# PCB_MOTEUR_V0_1b.net
KiCad netlist of a schematic drawn in EAGLE
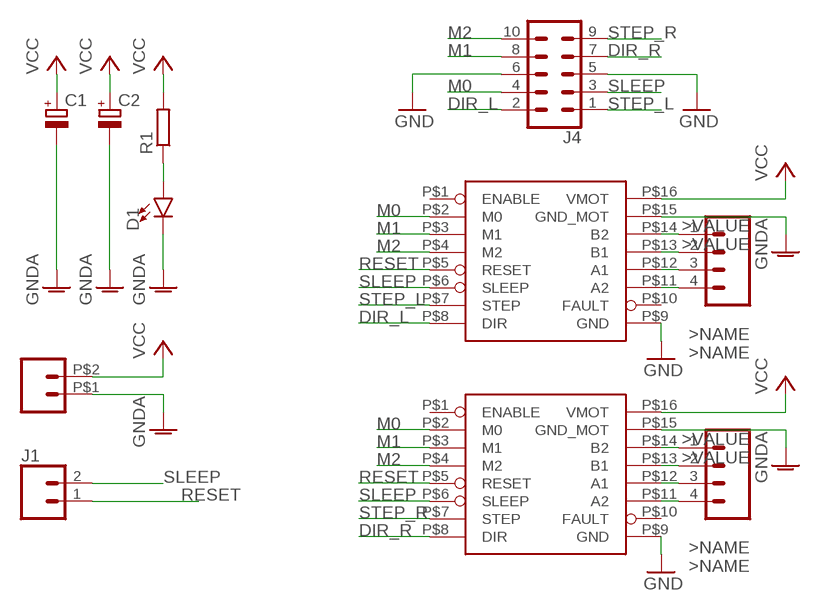
[diagram p0: schematic, sheet 1]

(export (version "E")
  (design (tool "Eeschema 10.0.6"))
  (components
    (comp (ref "C1")
      (value "CPOL-EUE3.5-8")
      (footprint "eagle-import:E3,5-8")
      (libsource (lib "eagle-import") (part "CPOL-EUE3.5-8"))
    )
    (comp (ref "C2")
      (value "CPOL-EUE3.5-8")
      (footprint "eagle-import:E3,5-8")
      (libsource (lib "eagle-import") (part "CPOL-EUE3.5-8"))
    )
    (comp (ref "D1")
      (value "LED3MM")
      (footprint "eagle-import:LED_3MM")
      (libsource (lib "eagle-import") (part "LED3MM"))
    )
    (comp (ref "J1")
      (value "CONN_02")
      (footprint "eagle-import:1X02")
      (libsource (lib "eagle-import") (part "CONN_02"))
    )
    (comp (ref "J2")
      (value "CONN_027A-C")
      (footprint "eagle-import:NSK396-2C")
      (libsource (lib "eagle-import") (part "CONN_027A-C"))
    )
    (comp (ref "J3")
      (value "CONN_04POLAR")
      (footprint "eagle-import:MOLEX-1X4")
      (libsource (lib "eagle-import") (part "CONN_04POLAR"))
    )
    (comp (ref "J4")
      (value "CONN_05X2SHD")
      (footprint "eagle-import:2X5-SHROUDED")
      (libsource (lib "eagle-import") (part "CONN_05X2SHD"))
    )
    (comp (ref "J5")
      (value "CONN_04POLAR")
      (footprint "eagle-import:MOLEX-1X4")
      (libsource (lib "eagle-import") (part "CONN_04POLAR"))
    )
    (comp (ref "R1")
      (value "R-EU_0207/2V")
      (footprint "eagle-import:0207_2V")
      (libsource (lib "eagle-import") (part "R-EU_0207/2V"))
    )
    (comp (ref "U$1")
      (value "DRV8825")
      (footprint "eagle-import:DRIVER_CARRIER_POLOLU_16")
      (libsource (lib "eagle-import") (part "DRV8825"))
    )
    (comp (ref "U$2")
      (value "DRV8825")
      (footprint "eagle-import:DRIVER_CARRIER_POLOLU_16")
      (libsource (lib "eagle-import") (part "DRV8825"))
    )
  )
  (nets
    (net (code "1") (name "/DIR_L") (class "Default")
      (node (ref "J4") (pin "2") (pinfunction "2_2") (pintype "passive"))
      (node (ref "U$1") (pin "P$8") (pinfunction "DIR_P$8") (pintype "bidirectional"))
    )
    (net (code "2") (name "/DIR_R") (class "Default")
      (node (ref "J4") (pin "7") (pinfunction "7_7") (pintype "passive"))
      (node (ref "U$2") (pin "P$8") (pinfunction "DIR_P$8") (pintype "bidirectional"))
    )
    (net (code "3") (name "/M0") (class "Default")
      (node (ref "J4") (pin "4") (pinfunction "4_4") (pintype "passive"))
      (node (ref "U$1") (pin "P$2") (pinfunction "M0_P$2") (pintype "bidirectional"))
      (node (ref "U$2") (pin "P$2") (pinfunction "M0_P$2") (pintype "bidirectional"))
    )
    (net (code "4") (name "/M1") (class "Default")
      (node (ref "J4") (pin "8") (pinfunction "8_8") (pintype "passive"))
      (node (ref "U$1") (pin "P$3") (pinfunction "M1_P$3") (pintype "bidirectional"))
      (node (ref "U$2") (pin "P$3") (pinfunction "M1_P$3") (pintype "bidirectional"))
    )
    (net (code "5") (name "/M2") (class "Default")
      (node (ref "J4") (pin "10") (pinfunction "10_10") (pintype "passive"))
      (node (ref "U$1") (pin "P$4") (pinfunction "M2_P$4") (pintype "bidirectional"))
      (node (ref "U$2") (pin "P$4") (pinfunction "M2_P$4") (pintype "bidirectional"))
    )
    (net (code "6") (name "/RESET") (class "Default")
      (node (ref "J1") (pin "1") (pinfunction "1_1") (pintype "passive"))
      (node (ref "U$1") (pin "P$5") (pinfunction "RESET_P$5") (pintype "bidirectional"))
      (node (ref "U$2") (pin "P$5") (pinfunction "RESET_P$5") (pintype "bidirectional"))
    )
    (net (code "7") (name "/SLEEP") (class "Default")
      (node (ref "J1") (pin "2") (pinfunction "2_2") (pintype "passive"))
      (node (ref "J4") (pin "3") (pinfunction "3_3") (pintype "passive"))
      (node (ref "U$1") (pin "P$6") (pinfunction "SLEEP_P$6") (pintype "bidirectional"))
      (node (ref "U$2") (pin "P$6") (pinfunction "SLEEP_P$6") (pintype "bidirectional"))
    )
    (net (code "8") (name "/STEP_L") (class "Default")
      (node (ref "J4") (pin "1") (pinfunction "1_1") (pintype "passive"))
      (node (ref "U$1") (pin "P$7") (pinfunction "STEP_P$7") (pintype "bidirectional"))
    )
    (net (code "9") (name "/STEP_R") (class "Default")
      (node (ref "J4") (pin "9") (pinfunction "9_9") (pintype "passive"))
      (node (ref "U$2") (pin "P$7") (pinfunction "STEP_P$7") (pintype "bidirectional"))
    )
    (net (code "10") (name "GND") (class "Default")
      (node (ref "J4") (pin "5") (pinfunction "5_5") (pintype "passive"))
      (node (ref "J4") (pin "6") (pinfunction "6_6") (pintype "passive"))
      (node (ref "U$1") (pin "P$9") (pinfunction "GND_P$9") (pintype "bidirectional"))
      (node (ref "U$2") (pin "P$9") (pinfunction "GND_P$9") (pintype "bidirectional"))
    )
    (net (code "11") (name "GNDA") (class "Default")
      (node (ref "C1") (pin "-") (pinfunction "-_-") (pintype "passive"))
      (node (ref "C2") (pin "-") (pinfunction "-_-") (pintype "passive"))
      (node (ref "D1") (pin "K") (pinfunction "C_K") (pintype "passive"))
      (node (ref "J2") (pin "P$1") (pinfunction "1_P$1") (pintype "passive"))
      (node (ref "U$1") (pin "P$15") (pinfunction "GND_MOT_P$15") (pintype "bidirectional"))
      (node (ref "U$2") (pin "P$15") (pinfunction "GND_MOT_P$15") (pintype "bidirectional"))
    )
    (net (code "12") (name "Net-(D1-PadA)") (class "Default")
      (node (ref "D1") (pin "A") (pinfunction "A_A") (pintype "passive"))
      (node (ref "R1") (pin "1") (pinfunction "1_1") (pintype "passive"))
    )
    (net (code "13") (name "Net-(U$1-A1)") (class "Default")
      (node (ref "J3") (pin "3") (pinfunction "3_3") (pintype "passive"))
      (node (ref "U$1") (pin "P$12") (pinfunction "A1_P$12") (pintype "bidirectional"))
    )
    (net (code "14") (name "Net-(U$1-A2)") (class "Default")
      (node (ref "J3") (pin "4") (pinfunction "4_4") (pintype "passive"))
      (node (ref "U$1") (pin "P$11") (pinfunction "A2_P$11") (pintype "bidirectional"))
    )
    (net (code "15") (name "Net-(U$1-B1)") (class "Default")
      (node (ref "J3") (pin "2") (pinfunction "2_2") (pintype "passive"))
      (node (ref "U$1") (pin "P$13") (pinfunction "B1_P$13") (pintype "bidirectional"))
    )
    (net (code "16") (name "Net-(U$1-B2)") (class "Default")
      (node (ref "J3") (pin "1") (pinfunction "1_1") (pintype "passive"))
      (node (ref "U$1") (pin "P$14") (pinfunction "B2_P$14") (pintype "bidirectional"))
    )
    (net (code "17") (name "Net-(U$2-A1)") (class "Default")
      (node (ref "J5") (pin "3") (pinfunction "3_3") (pintype "passive"))
      (node (ref "U$2") (pin "P$12") (pinfunction "A1_P$12") (pintype "bidirectional"))
    )
    (net (code "18") (name "Net-(U$2-A2)") (class "Default")
      (node (ref "J5") (pin "4") (pinfunction "4_4") (pintype "passive"))
      (node (ref "U$2") (pin "P$11") (pinfunction "A2_P$11") (pintype "bidirectional"))
    )
    (net (code "19") (name "Net-(U$2-B1)") (class "Default")
      (node (ref "J5") (pin "2") (pinfunction "2_2") (pintype "passive"))
      (node (ref "U$2") (pin "P$13") (pinfunction "B1_P$13") (pintype "bidirectional"))
    )
    (net (code "20") (name "Net-(U$2-B2)") (class "Default")
      (node (ref "J5") (pin "1") (pinfunction "1_1") (pintype "passive"))
      (node (ref "U$2") (pin "P$14") (pinfunction "B2_P$14") (pintype "bidirectional"))
    )
    (net (code "21") (name "VCC") (class "Default")
      (node (ref "C1") (pin "+") (pinfunction "+_+") (pintype "passive"))
      (node (ref "C2") (pin "+") (pinfunction "+_+") (pintype "passive"))
      (node (ref "J2") (pin "P$2") (pinfunction "2_P$2") (pintype "passive"))
      (node (ref "R1") (pin "2") (pinfunction "2_2") (pintype "passive"))
      (node (ref "U$1") (pin "P$16") (pinfunction "VMOT_P$16") (pintype "bidirectional"))
      (node (ref "U$2") (pin "P$16") (pinfunction "VMOT_P$16") (pintype "bidirectional"))
    )
    (net (code "22") (name "unconnected-(U$1-ENABLE-PadP$1)") (class "Default")
      (node (ref "U$1") (pin "P$1") (pinfunction "ENABLE_P$1") (pintype "bidirectional"))
    )
    (net (code "23") (name "unconnected-(U$1-FAULT-PadP$10)") (class "Default")
      (node (ref "U$1") (pin "P$10") (pinfunction "FAULT_P$10") (pintype "bidirectional"))
    )
    (net (code "24") (name "unconnected-(U$2-ENABLE-PadP$1)") (class "Default")
      (node (ref "U$2") (pin "P$1") (pinfunction "ENABLE_P$1") (pintype "bidirectional"))
    )
    (net (code "25") (name "unconnected-(U$2-FAULT-PadP$10)") (class "Default")
      (node (ref "U$2") (pin "P$10") (pinfunction "FAULT_P$10") (pintype "bidirectional"))
    )
  )
)
